# MCU.net
KiCad netlist of a schematic drawn in Altium Designer
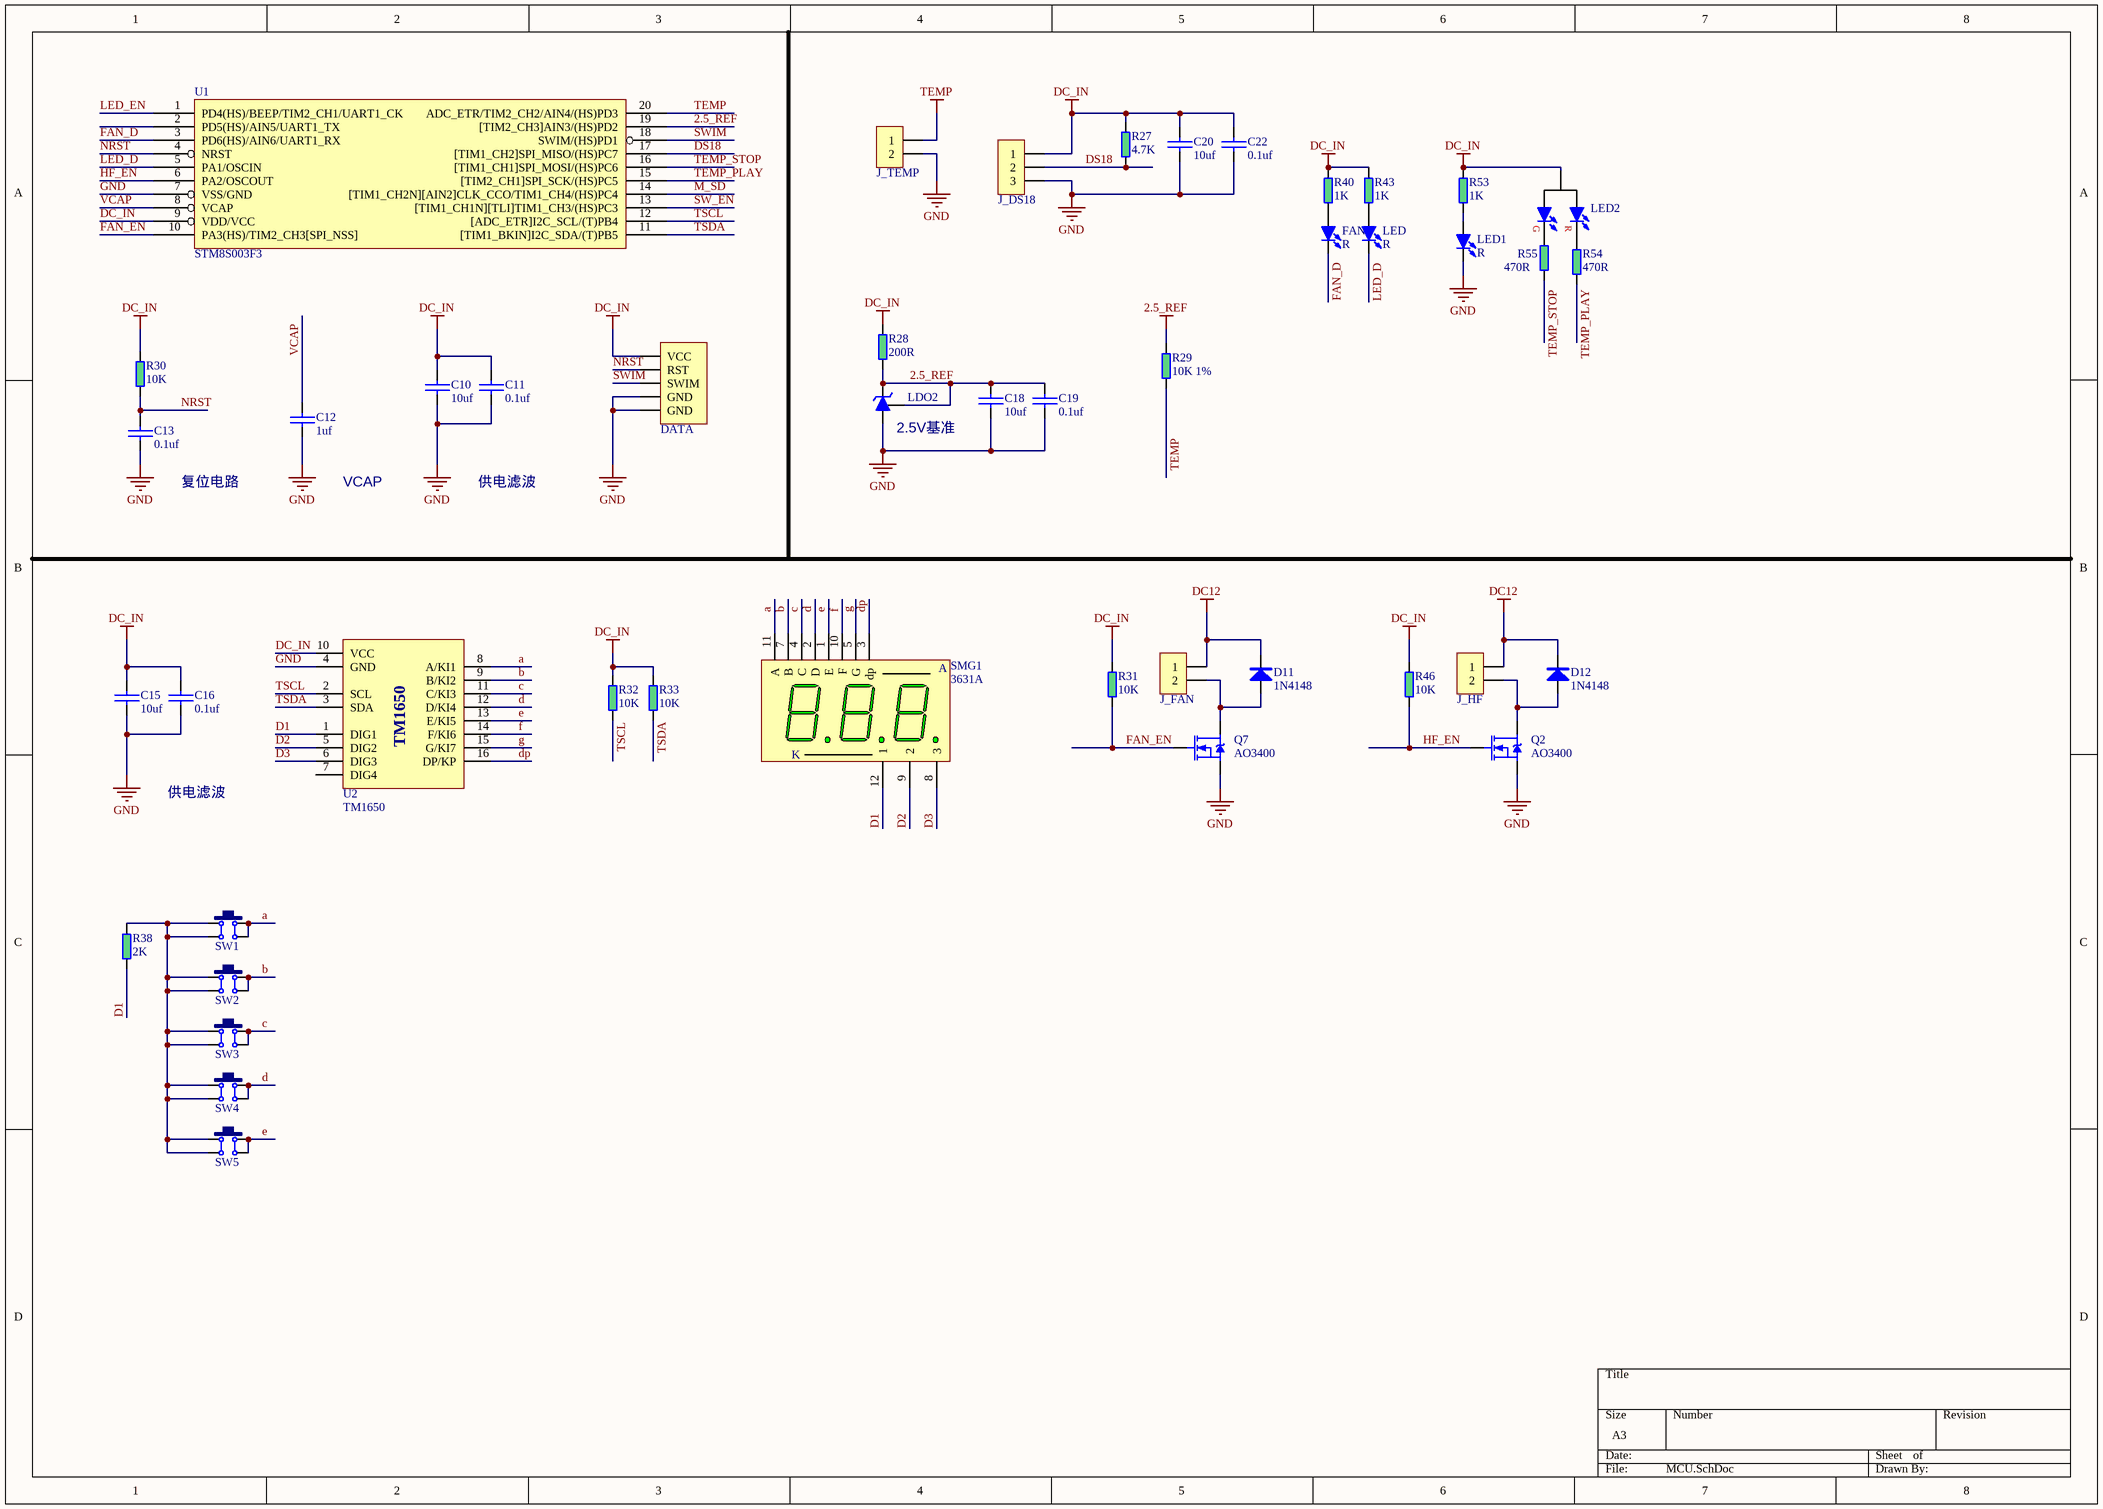
[diagram p0: MCU.SchDoc]

(export (version "E")
  (design (tool "Eeschema 10.0.6"))
  (components
    (comp (ref "C10")
      (value "10uf")
      (footprint "C 0603")
      (description "电容")
      (fields (field (name "Comment") "04.Cap"))
      (libsource (lib "电子元件") (part "04.Cap"))
    )
    (comp (ref "C11")
      (value "0.1uf")
      (footprint "C 0603")
      (description "电容")
      (fields (field (name "Comment") "04.Cap"))
      (libsource (lib "电子元件") (part "04.Cap"))
    )
    (comp (ref "C12")
      (value "1uf")
      (footprint "C 0603")
      (description "电容")
      (fields (field (name "Comment") "04.Cap"))
      (libsource (lib "电子元件") (part "04.Cap"))
    )
    (comp (ref "C13")
      (value "0.1uf")
      (footprint "C 0603")
      (description "电容")
      (fields (field (name "Comment") "04.Cap"))
      (libsource (lib "电子元件") (part "04.Cap"))
    )
    (comp (ref "C15")
      (value "10uf")
      (footprint "C 0603")
      (description "电容")
      (fields (field (name "Comment") "04.Cap"))
      (libsource (lib "电子元件") (part "04.Cap"))
    )
    (comp (ref "C16")
      (value "0.1uf")
      (footprint "C 0603")
      (description "电容")
      (fields (field (name "Comment") "04.Cap"))
      (libsource (lib "电子元件") (part "04.Cap"))
    )
    (comp (ref "C18")
      (value "10uf")
      (footprint "C 0603")
      (description "电容")
      (fields (field (name "Comment") "04.Cap"))
      (libsource (lib "电子元件") (part "04.Cap"))
    )
    (comp (ref "C19")
      (value "0.1uf")
      (footprint "C 0603")
      (description "电容")
      (fields (field (name "Comment") "04.Cap"))
      (libsource (lib "电子元件") (part "04.Cap"))
    )
    (comp (ref "C20")
      (value "10uf")
      (footprint "C 0603")
      (description "电容")
      (fields (field (name "Comment") "04.Cap"))
      (libsource (lib "电子元件") (part "04.Cap"))
    )
    (comp (ref "C22")
      (value "0.1uf")
      (footprint "C 0603")
      (description "电容")
      (fields (field (name "Comment") "04.Cap"))
      (libsource (lib "电子元件") (part "04.Cap"))
    )
    (comp (ref "D11")
      (value "1N4148")
      (footprint "D 1N4148-LL34")
      (description "二极管")
      (libsource (lib "电子元件") (part "12.Diode"))
    )
    (comp (ref "D12")
      (value "1N4148")
      (footprint "D 1N4148-LL34")
      (description "二极管")
      (libsource (lib "电子元件") (part "12.Diode"))
    )
    (comp (ref "DATA")
      (value "WR_STM-SWIM")
      (footprint "MCU_WRITE")
      (libsource (lib "接插件") (part "WR_STM-SWIM"))
    )
    (comp (ref "FAN")
      (value "R")
      (footprint "LED 0603B")
      (description "LED")
      (libsource (lib "电子元件") (part "15.Diode - LED"))
    )
    (comp (ref "J_DS18") (value "Pin03") (footprint "XH2.54 3P") (libsource (lib "接插件") (part "Pin03")))
    (comp (ref "J_FAN") (value "Pin02") (footprint "XH2.54 2P") (libsource (lib "接插件") (part "Pin02")))
    (comp (ref "J_HF") (value "Pin02") (footprint "XH2.54 2P") (libsource (lib "接插件") (part "Pin02")))
    (comp (ref "J_TEMP") (value "Pin02") (footprint "XH2.54 2P") (libsource (lib "接插件") (part "Pin02")))
    (comp (ref "LDO2")
      (value "TL431")
      (footprint "P TL431-SOT23")
      (description "电压基准（out=Ref*(1+R1/R2)）")
      (libsource (lib "集成IC") (part "TL431"))
    )
    (comp (ref "LED")
      (value "R")
      (footprint "LED 0603B")
      (description "LED")
      (libsource (lib "电子元件") (part "15.Diode - LED"))
    )
    (comp (ref "LED1")
      (value "R")
      (footprint "LED 3mm R")
      (description "LED")
      (libsource (lib "电子元件") (part "15.Diode - LED"))
    )
    (comp (ref "LED2")
      (value "15.Diode - PLED - double")
      (footprint "LED 3mm R/G")
      (libsource (lib "电子元件") (part "15.Diode - PLED - double"))
    )
    (comp (ref "Q2")
      (value "AO3400")
      (footprint "FET-AO3400-SOT23")
      (description "MOS管 NPN")
      (libsource (lib "电子元件") (part "09.FET(N)"))
    )
    (comp (ref "Q7")
      (value "AO3400")
      (footprint "FET-AO3400-SOT23")
      (description "MOS管 NPN")
      (libsource (lib "电子元件") (part "09.FET(N)"))
    )
    (comp (ref "R27")
      (value "4.7K")
      (footprint "R 0603")
      (description "电阻")
      (libsource (lib "电子元件") (part "01.Res"))
    )
    (comp (ref "R28")
      (value "200R")
      (footprint "R 0603")
      (description "电阻")
      (libsource (lib "电子元件") (part "01.Res"))
    )
    (comp (ref "R29")
      (value "10K 1%")
      (footprint "R 0805")
      (description "电阻")
      (libsource (lib "电子元件") (part "01.Res"))
    )
    (comp (ref "R30")
      (value "10K")
      (footprint "R 0603")
      (description "电阻")
      (libsource (lib "电子元件") (part "01.Res"))
    )
    (comp (ref "R31")
      (value "10K")
      (footprint "R 0603")
      (description "电阻")
      (libsource (lib "电子元件") (part "01.Res"))
    )
    (comp (ref "R32")
      (value "10K")
      (footprint "R 0603")
      (description "电阻")
      (libsource (lib "电子元件") (part "01.Res"))
    )
    (comp (ref "R33")
      (value "10K")
      (footprint "R 0603")
      (description "电阻")
      (libsource (lib "电子元件") (part "01.Res"))
    )
    (comp (ref "R38")
      (value "2K")
      (footprint "R 0603")
      (description "电阻")
      (libsource (lib "电子元件") (part "01.Res"))
    )
    (comp (ref "R40")
      (value "1K")
      (footprint "R 0603")
      (description "电阻")
      (libsource (lib "电子元件") (part "01.Res"))
    )
    (comp (ref "R43")
      (value "1K")
      (footprint "R 0603")
      (description "电阻")
      (libsource (lib "电子元件") (part "01.Res"))
    )
    (comp (ref "R46")
      (value "10K")
      (footprint "R 0603")
      (description "电阻")
      (libsource (lib "电子元件") (part "01.Res"))
    )
    (comp (ref "R53")
      (value "1K")
      (footprint "R 0603")
      (description "电阻")
      (libsource (lib "电子元件") (part "01.Res"))
    )
    (comp (ref "R54")
      (value "470R")
      (footprint "R 0603")
      (description "电阻")
      (libsource (lib "电子元件") (part "01.Res"))
    )
    (comp (ref "R55")
      (value "470R")
      (footprint "R 0603")
      (description "电阻")
      (libsource (lib "电子元件") (part "01.Res"))
    )
    (comp (ref "SMG1")
      (value "3631A")
      (footprint "SMG 0.36-3P")
      (description "0.36寸3位共阴数码管")
      (fields (field (name "版权归属") "源创客"))
      (libsource (lib "显示器件") (part "3631A"))
    )
    (comp (ref "SW1")
      (value "TSW DIP-6x6")
      (footprint "TSW DIP-6*6")
      (description "6x6轻触开关")
      (libsource (lib "按钮开关") (part "TSW DIP-6x6"))
    )
    (comp (ref "SW2")
      (value "TSW DIP-6x6")
      (footprint "TSW DIP-6*6")
      (description "6x6轻触开关")
      (libsource (lib "按钮开关") (part "TSW DIP-6x6"))
    )
    (comp (ref "SW3")
      (value "TSW DIP-6x6")
      (footprint "TSW DIP-6*6")
      (description "6x6轻触开关")
      (libsource (lib "按钮开关") (part "TSW DIP-6x6"))
    )
    (comp (ref "SW4")
      (value "TSW DIP-6x6")
      (footprint "TSW DIP-6*6")
      (description "6x6轻触开关")
      (libsource (lib "按钮开关") (part "TSW DIP-6x6"))
    )
    (comp (ref "SW5")
      (value "TSW DIP-6x6")
      (footprint "TSW DIP-6*6")
      (description "6x6轻触开关")
      (libsource (lib "按钮开关") (part "TSW DIP-6x6"))
    )
    (comp (ref "U1")
      (value "STM8S003F3")
      (footprint "TSSOP20")
      (libsource (lib "单片机") (part "STM8S003F3P6 - TSSOP20"))
    )
    (comp (ref "U2")
      (value "TM1650")
      (footprint "SOP16")
      (description "数码管驱动芯片")
      (libsource (lib "集成IC") (part "TM1650"))
    )
  )
  (nets
    (net (code "1") (name "/D1") (class "Default")
      (node (ref "R38") (pin "1") (pinfunction "1_1") (pintype "passive"))
      (node (ref "SMG1") (pin "12") (pinfunction "1_12") (pintype "passive"))
      (node (ref "U2") (pin "1") (pinfunction "DIG1_1") (pintype "passive"))
    )
    (net (code "2") (name "/D2") (class "Default")
      (node (ref "SMG1") (pin "9") (pinfunction "2_9") (pintype "passive"))
      (node (ref "U2") (pin "5") (pinfunction "DIG2_5") (pintype "passive"))
    )
    (net (code "3") (name "/D3") (class "Default")
      (node (ref "SMG1") (pin "8") (pinfunction "3_8") (pintype "passive"))
      (node (ref "U2") (pin "6") (pinfunction "DIG3_6") (pintype "passive"))
    )
    (net (code "4") (name "/DS18") (class "Default")
      (node (ref "J_DS18") (pin "2") (pinfunction "2_2") (pintype "passive"))
      (node (ref "R27") (pin "1") (pinfunction "1_1") (pintype "passive"))
      (node (ref "U1") (pin "17") (pinfunction "[TIM1_CH2]SPI_MISO/(HS)PC7_17") (pintype "passive"))
    )
    (net (code "5") (name "/FAN_D") (class "Default")
      (node (ref "FAN") (pin "K") (pinfunction "K_K") (pintype "passive"))
      (node (ref "U1") (pin "3") (pinfunction "PD6(HS)/AIN6/UART1_RX_3") (pintype "passive"))
    )
    (net (code "6") (name "/FAN_EN") (class "Default")
      (node (ref "Q7") (pin "G") (pinfunction "G_G") (pintype "passive"))
      (node (ref "R31") (pin "1") (pinfunction "1_1") (pintype "passive"))
      (node (ref "U1") (pin "10") (pinfunction "PA3(HS)/TIM2_CH3[SPI_NSS]_10") (pintype "passive"))
    )
    (net (code "7") (name "/HF_EN") (class "Default")
      (node (ref "Q2") (pin "G") (pinfunction "G_G") (pintype "passive"))
      (node (ref "R46") (pin "1") (pinfunction "1_1") (pintype "passive"))
      (node (ref "U1") (pin "6") (pinfunction "PA2/OSCOUT_6") (pintype "passive"))
    )
    (net (code "8") (name "/LED_D") (class "Default")
      (node (ref "LED") (pin "K") (pinfunction "K_K") (pintype "passive"))
      (node (ref "U1") (pin "5") (pinfunction "PA1/OSCIN_5") (pintype "passive"))
    )
    (net (code "9") (name "/LED_EN") (class "Default")
      (node (ref "U1") (pin "1") (pinfunction "PD4(HS)/BEEP/TIM2_CH1/UART1_CK_1") (pintype "passive"))
    )
    (net (code "10") (name "/M_SD") (class "Default")
      (node (ref "U1") (pin "14") (pinfunction "[TIM1_CH2N][AIN2]CLK_CCO/TIM1_CH4/(HS)PC4_14") (pintype "passive"))
    )
    (net (code "11") (name "/NRST") (class "Default")
      (node (ref "C13") (pin "1") (pinfunction "1_1") (pintype "passive"))
      (node (ref "DATA") (pin "2") (pinfunction "RST_2") (pintype "passive"))
      (node (ref "R30") (pin "1") (pinfunction "1_1") (pintype "passive"))
      (node (ref "U1") (pin "4") (pinfunction "NRST_4") (pintype "passive"))
    )
    (net (code "12") (name "/SWIM") (class "Default")
      (node (ref "DATA") (pin "3") (pinfunction "SWIM_3") (pintype "passive"))
      (node (ref "U1") (pin "18") (pinfunction "SWIM/(HS)PD1_18") (pintype "passive"))
    )
    (net (code "13") (name "/SW_EN") (class "Default")
      (node (ref "U1") (pin "13") (pinfunction "[TIM1_CH1N][TLI]TIM1_CH3/(HS)PC3_13") (pintype "passive"))
    )
    (net (code "14") (name "/TEMP_PLAY") (class "Default")
      (node (ref "R54") (pin "1") (pinfunction "1_1") (pintype "passive"))
      (node (ref "U1") (pin "15") (pinfunction "[TIM2_CH1]SPI_SCK/(HS)PC5_15") (pintype "passive"))
    )
    (net (code "15") (name "/TEMP_STOP") (class "Default")
      (node (ref "R55") (pin "1") (pinfunction "1_1") (pintype "passive"))
      (node (ref "U1") (pin "16") (pinfunction "[TIM1_CH1]SPI_MOSI/(HS)PC6_16") (pintype "passive"))
    )
    (net (code "16") (name "/TSCL") (class "Default")
      (node (ref "R32") (pin "1") (pinfunction "1_1") (pintype "passive"))
      (node (ref "U1") (pin "12") (pinfunction "[ADC_ETR]I2C_SCL/(T)PB4_12") (pintype "passive"))
      (node (ref "U2") (pin "2") (pinfunction "SCL_2") (pintype "passive"))
    )
    (net (code "17") (name "/TSDA") (class "Default")
      (node (ref "R33") (pin "1") (pinfunction "1_1") (pintype "passive"))
      (node (ref "U1") (pin "11") (pinfunction "[TIM1_BKIN]I2C_SDA/(T)PB5_11") (pintype "passive"))
      (node (ref "U2") (pin "3") (pinfunction "SDA_3") (pintype "passive"))
    )
    (net (code "18") (name "/VCAP") (class "Default")
      (node (ref "C12") (pin "1") (pinfunction "1_1") (pintype "passive"))
      (node (ref "U1") (pin "8") (pinfunction "VCAP_8") (pintype "passive"))
    )
    (net (code "19") (name "/a") (class "Default")
      (node (ref "SMG1") (pin "11") (pinfunction "A_11") (pintype "passive"))
      (node (ref "SW1") (pin "C") (pinfunction "C_C") (pintype "passive"))
      (node (ref "SW1") (pin "D") (pinfunction "D_D") (pintype "passive"))
      (node (ref "U2") (pin "8") (pinfunction "A/KI1_8") (pintype "passive"))
    )
    (net (code "20") (name "/b") (class "Default")
      (node (ref "SMG1") (pin "7") (pinfunction "B_7") (pintype "passive"))
      (node (ref "SW2") (pin "C") (pinfunction "C_C") (pintype "passive"))
      (node (ref "SW2") (pin "D") (pinfunction "D_D") (pintype "passive"))
      (node (ref "U2") (pin "9") (pinfunction "B/KI2_9") (pintype "passive"))
    )
    (net (code "21") (name "/c") (class "Default")
      (node (ref "SMG1") (pin "4") (pinfunction "C_4") (pintype "passive"))
      (node (ref "SW3") (pin "C") (pinfunction "C_C") (pintype "passive"))
      (node (ref "SW3") (pin "D") (pinfunction "D_D") (pintype "passive"))
      (node (ref "U2") (pin "11") (pinfunction "C/KI3_11") (pintype "passive"))
    )
    (net (code "22") (name "/d") (class "Default")
      (node (ref "SMG1") (pin "2") (pinfunction "D_2") (pintype "passive"))
      (node (ref "SW4") (pin "C") (pinfunction "C_C") (pintype "passive"))
      (node (ref "SW4") (pin "D") (pinfunction "D_D") (pintype "passive"))
      (node (ref "U2") (pin "12") (pinfunction "D/KI4_12") (pintype "passive"))
    )
    (net (code "23") (name "/dp") (class "Default")
      (node (ref "SMG1") (pin "3") (pinfunction "dp_3") (pintype "passive"))
      (node (ref "U2") (pin "16") (pinfunction "DP/KP_16") (pintype "passive"))
    )
    (net (code "24") (name "/e") (class "Default")
      (node (ref "SMG1") (pin "1") (pinfunction "E_1") (pintype "passive"))
      (node (ref "SW5") (pin "C") (pinfunction "C_C") (pintype "passive"))
      (node (ref "SW5") (pin "D") (pinfunction "D_D") (pintype "passive"))
      (node (ref "U2") (pin "13") (pinfunction "E/KI5_13") (pintype "passive"))
    )
    (net (code "25") (name "/f") (class "Default")
      (node (ref "SMG1") (pin "10") (pinfunction "F_10") (pintype "passive"))
      (node (ref "U2") (pin "14") (pinfunction "F/KI6_14") (pintype "passive"))
    )
    (net (code "26") (name "/g") (class "Default")
      (node (ref "SMG1") (pin "5") (pinfunction "G_5") (pintype "passive"))
      (node (ref "U2") (pin "15") (pinfunction "G/KI7_15") (pintype "passive"))
    )
    (net (code "27") (name "2.5_REF") (class "Default")
      (node (ref "C18") (pin "1") (pinfunction "1_1") (pintype "passive"))
      (node (ref "C19") (pin "1") (pinfunction "1_1") (pintype "passive"))
      (node (ref "LDO2") (pin "K") (pinfunction "K_K") (pintype "passive"))
      (node (ref "LDO2") (pin "R") (pinfunction "R_R") (pintype "passive"))
      (node (ref "R28") (pin "1") (pinfunction "1_1") (pintype "passive"))
      (node (ref "R29") (pin "2") (pinfunction "2_2") (pintype "passive"))
      (node (ref "U1") (pin "19") (pinfunction "[TIM2_CH3]AIN3/(HS)PD2_19") (pintype "passive"))
    )
    (net (code "28") (name "DC12") (class "Default")
      (node (ref "D11") (pin "K") (pinfunction "K_K") (pintype "passive"))
      (node (ref "D12") (pin "K") (pinfunction "K_K") (pintype "passive"))
      (node (ref "J_FAN") (pin "1") (pinfunction "1_1") (pintype "passive"))
      (node (ref "J_HF") (pin "1") (pinfunction "1_1") (pintype "passive"))
    )
    (net (code "29") (name "DC_IN") (class "Default")
      (node (ref "C10") (pin "1") (pinfunction "1_1") (pintype "passive"))
      (node (ref "C11") (pin "1") (pinfunction "1_1") (pintype "passive"))
      (node (ref "C15") (pin "1") (pinfunction "1_1") (pintype "passive"))
      (node (ref "C16") (pin "1") (pinfunction "1_1") (pintype "passive"))
      (node (ref "C20") (pin "1") (pinfunction "1_1") (pintype "passive"))
      (node (ref "C22") (pin "1") (pinfunction "1_1") (pintype "passive"))
      (node (ref "DATA") (pin "1") (pinfunction "VCC_1") (pintype "passive"))
      (node (ref "J_DS18") (pin "1") (pinfunction "1_1") (pintype "passive"))
      (node (ref "LED2") (pin "A") (pinfunction "A_A") (pintype "passive"))
      (node (ref "R27") (pin "2") (pinfunction "2_2") (pintype "passive"))
      (node (ref "R28") (pin "2") (pinfunction "2_2") (pintype "passive"))
      (node (ref "R30") (pin "2") (pinfunction "2_2") (pintype "passive"))
      (node (ref "R31") (pin "2") (pinfunction "2_2") (pintype "passive"))
      (node (ref "R32") (pin "2") (pinfunction "2_2") (pintype "passive"))
      (node (ref "R33") (pin "2") (pinfunction "2_2") (pintype "passive"))
      (node (ref "R40") (pin "2") (pinfunction "2_2") (pintype "passive"))
      (node (ref "R43") (pin "2") (pinfunction "2_2") (pintype "passive"))
      (node (ref "R46") (pin "2") (pinfunction "2_2") (pintype "passive"))
      (node (ref "R53") (pin "2") (pinfunction "2_2") (pintype "passive"))
      (node (ref "U1") (pin "9") (pinfunction "VDD/VCC_9") (pintype "passive"))
      (node (ref "U2") (pin "10") (pinfunction "VCC_10") (pintype "passive"))
    )
    (net (code "30") (name "GND") (class "Default")
      (node (ref "C10") (pin "2") (pinfunction "2_2") (pintype "passive"))
      (node (ref "C11") (pin "2") (pinfunction "2_2") (pintype "passive"))
      (node (ref "C12") (pin "2") (pinfunction "2_2") (pintype "passive"))
      (node (ref "C13") (pin "2") (pinfunction "2_2") (pintype "passive"))
      (node (ref "C15") (pin "2") (pinfunction "2_2") (pintype "passive"))
      (node (ref "C16") (pin "2") (pinfunction "2_2") (pintype "passive"))
      (node (ref "C18") (pin "2") (pinfunction "2_2") (pintype "passive"))
      (node (ref "C19") (pin "2") (pinfunction "2_2") (pintype "passive"))
      (node (ref "C20") (pin "2") (pinfunction "2_2") (pintype "passive"))
      (node (ref "C22") (pin "2") (pinfunction "2_2") (pintype "passive"))
      (node (ref "DATA") (pin "4") (pinfunction "GND_4") (pintype "passive"))
      (node (ref "DATA") (pin "5") (pinfunction "GND_5") (pintype "passive"))
      (node (ref "J_DS18") (pin "3") (pinfunction "3_3") (pintype "passive"))
      (node (ref "J_TEMP") (pin "2") (pinfunction "2_2") (pintype "passive"))
      (node (ref "LDO2") (pin "A") (pinfunction "A_A") (pintype "passive"))
      (node (ref "LED1") (pin "K") (pinfunction "K_K") (pintype "passive"))
      (node (ref "Q2") (pin "S") (pinfunction "S_S") (pintype "passive"))
      (node (ref "Q7") (pin "S") (pinfunction "S_S") (pintype "passive"))
      (node (ref "U1") (pin "7") (pinfunction "VSS/GND_7") (pintype "passive"))
      (node (ref "U2") (pin "4") (pinfunction "GND_4") (pintype "passive"))
    )
    (net (code "31") (name "Net-(D11-PadA)") (class "Default")
      (node (ref "D11") (pin "A") (pinfunction "A_A") (pintype "passive"))
      (node (ref "J_FAN") (pin "2") (pinfunction "2_2") (pintype "passive"))
      (node (ref "Q7") (pin "D") (pinfunction "D_D") (pintype "passive"))
    )
    (net (code "32") (name "Net-(D12-PadA)") (class "Default")
      (node (ref "D12") (pin "A") (pinfunction "A_A") (pintype "passive"))
      (node (ref "J_HF") (pin "2") (pinfunction "2_2") (pintype "passive"))
      (node (ref "Q2") (pin "D") (pinfunction "D_D") (pintype "passive"))
    )
    (net (code "33") (name "Net-(FAN-PadA)") (class "Default")
      (node (ref "FAN") (pin "A") (pinfunction "A_A") (pintype "passive"))
      (node (ref "R40") (pin "1") (pinfunction "1_1") (pintype "passive"))
    )
    (net (code "34") (name "Net-(LED-PadA)") (class "Default")
      (node (ref "LED") (pin "A") (pinfunction "A_A") (pintype "passive"))
      (node (ref "R43") (pin "1") (pinfunction "1_1") (pintype "passive"))
    )
    (net (code "35") (name "Net-(LED1-PadA)") (class "Default")
      (node (ref "LED1") (pin "A") (pinfunction "A_A") (pintype "passive"))
      (node (ref "R53") (pin "1") (pinfunction "1_1") (pintype "passive"))
    )
    (net (code "36") (name "Net-(LED2-PadG)") (class "Default")
      (node (ref "LED2") (pin "G") (pinfunction "G_G") (pintype "passive"))
      (node (ref "R55") (pin "2") (pinfunction "2_2") (pintype "passive"))
    )
    (net (code "37") (name "Net-(LED2-PadR)") (class "Default")
      (node (ref "LED2") (pin "R") (pinfunction "R_R") (pintype "passive"))
      (node (ref "R54") (pin "2") (pinfunction "2_2") (pintype "passive"))
    )
    (net (code "38") (name "Net-(R38-Pad2)") (class "Default")
      (node (ref "R38") (pin "2") (pinfunction "2_2") (pintype "passive"))
      (node (ref "SW1") (pin "A") (pinfunction "A_A") (pintype "passive"))
      (node (ref "SW1") (pin "B") (pinfunction "B_B") (pintype "passive"))
      (node (ref "SW2") (pin "A") (pinfunction "A_A") (pintype "passive"))
      (node (ref "SW2") (pin "B") (pinfunction "B_B") (pintype "passive"))
      (node (ref "SW3") (pin "A") (pinfunction "A_A") (pintype "passive"))
      (node (ref "SW3") (pin "B") (pinfunction "B_B") (pintype "passive"))
      (node (ref "SW4") (pin "A") (pinfunction "A_A") (pintype "passive"))
      (node (ref "SW4") (pin "B") (pinfunction "B_B") (pintype "passive"))
      (node (ref "SW5") (pin "A") (pinfunction "A_A") (pintype "passive"))
      (node (ref "SW5") (pin "B") (pinfunction "B_B") (pintype "passive"))
    )
    (net (code "39") (name "TEMP") (class "Default")
      (node (ref "J_TEMP") (pin "1") (pinfunction "1_1") (pintype "passive"))
      (node (ref "R29") (pin "1") (pinfunction "1_1") (pintype "passive"))
      (node (ref "U1") (pin "20") (pinfunction "ADC_ETR/TIM2_CH2/AIN4/(HS)PD3_20") (pintype "passive"))
    )
    (net (code "40") (name "unconnected-(U1-PD5(HS){slash}AIN5{slash}UART1_TX-Pad2)") (class "Default")
      (node (ref "U1") (pin "2") (pinfunction "PD5(HS)/AIN5/UART1_TX_2") (pintype "passive"))
    )
    (net (code "41") (name "unconnected-(U2-DIG4-Pad7)") (class "Default")
      (node (ref "U2") (pin "7") (pinfunction "DIG4_7") (pintype "passive"))
    )
  )
)
